# CPU_board.net
KiCad netlist of a schematic drawn in Altium Designer
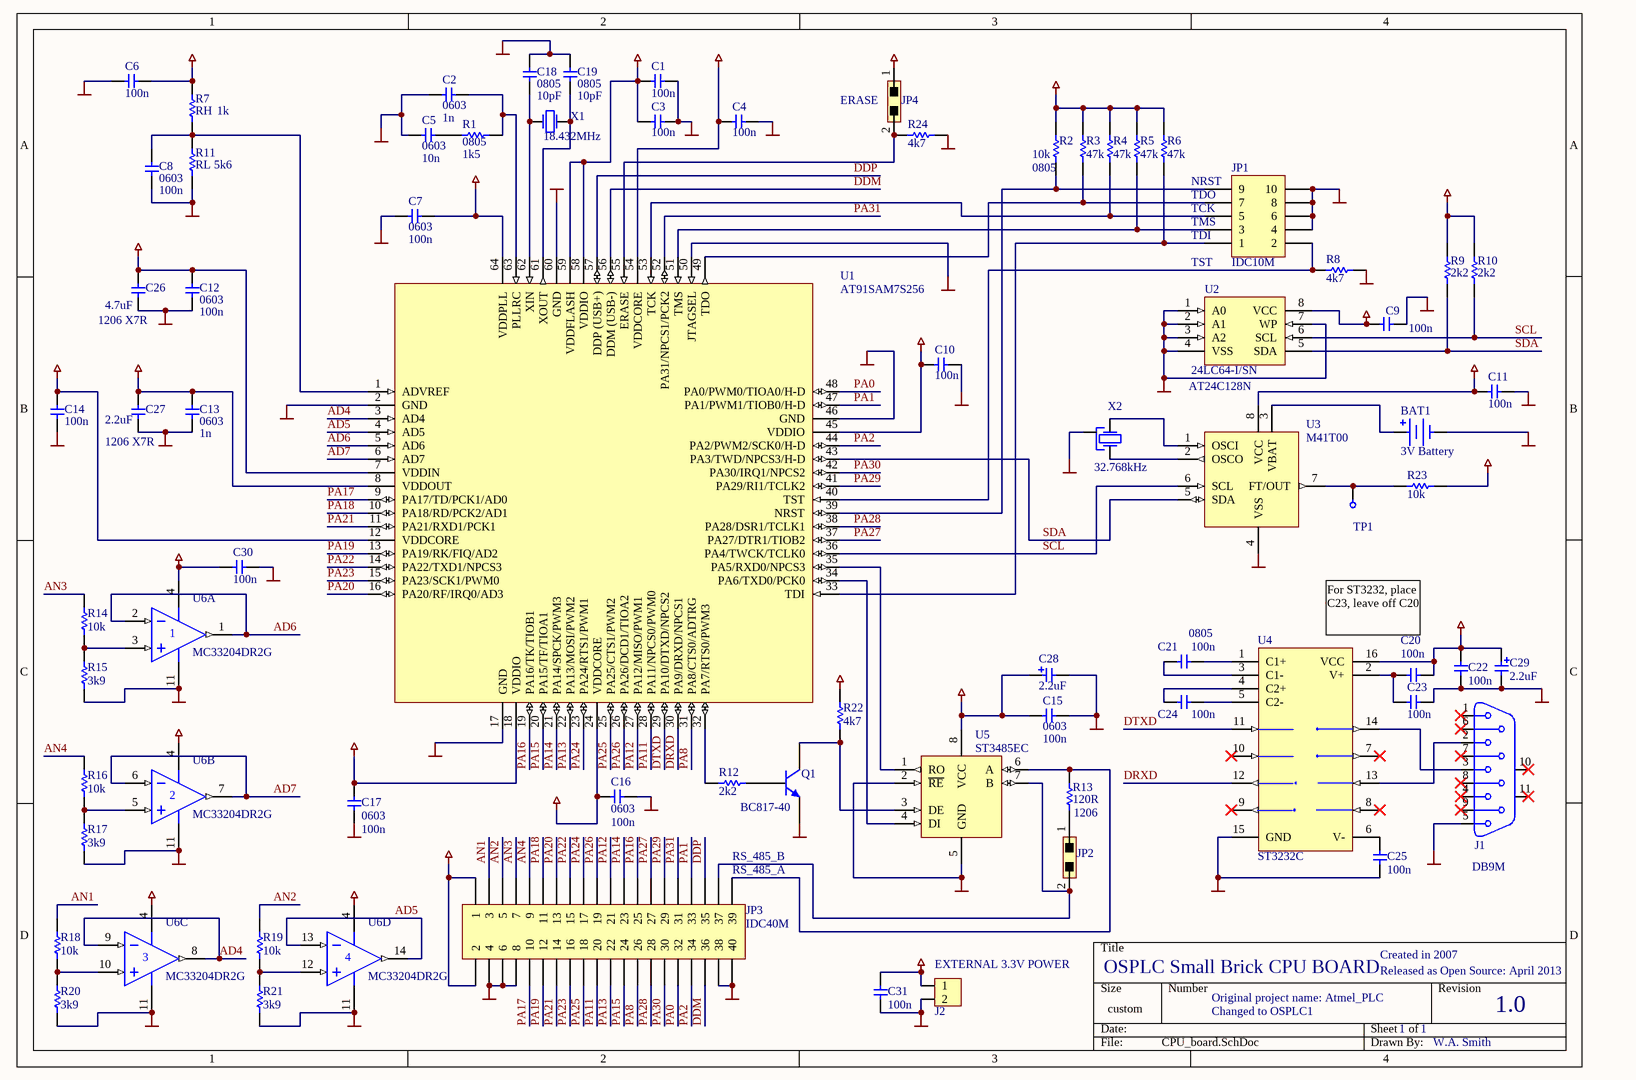
[diagram p0: CPU_board.SchDoc]

(export (version "E")
  (design (tool "Eeschema 10.0.6"))
  (components
    (comp (ref "BAT1")
      (value "3V Battery")
      (footprint "BATTERY_22MM")
      (description "3 Volt Lithium Button Battery")
      (libsource (lib "ARM_projects") (part "BATTERY_22MM"))
    )
    (comp (ref "C1")
      (value "0603")
      (footprint "0603")
      (description "0603 footprint non-polorised capacitor")
      (fields (field (name "ALTIUM_VALUE") "100n"))
      (libsource (lib "Integrated Comp_lib") (part "CAP_0603"))
    )
    (comp (ref "C2")
      (value "0603")
      (footprint "0603")
      (description "0603 footprint non-polorised capacitor")
      (fields (field (name "ALTIUM_VALUE") "1n"))
      (libsource (lib "Integrated Comp_lib") (part "CAP_0603"))
    )
    (comp (ref "C3")
      (value "0603")
      (footprint "0603")
      (description "0603 footprint non-polorised capacitor")
      (fields (field (name "ALTIUM_VALUE") "100n"))
      (libsource (lib "Integrated Comp_lib") (part "CAP_0603"))
    )
    (comp (ref "C4")
      (value "0603")
      (footprint "0603")
      (description "0603 footprint non-polorised capacitor")
      (fields (field (name "ALTIUM_VALUE") "100n"))
      (libsource (lib "Integrated Comp_lib") (part "CAP_0603"))
    )
    (comp (ref "C5")
      (value "0603")
      (footprint "0603")
      (description "0603 footprint non-polorised capacitor")
      (fields (field (name "ALTIUM_VALUE") "10n"))
      (libsource (lib "Integrated Comp_lib") (part "CAP_0603"))
    )
    (comp (ref "C6")
      (value "0603")
      (footprint "0603")
      (description "0603 footprint non-polorised capacitor")
      (fields (field (name "ALTIUM_VALUE") "100n"))
      (libsource (lib "Integrated Comp_lib") (part "CAP_0603"))
    )
    (comp (ref "C7")
      (value "0603")
      (footprint "0603")
      (description "0603 footprint non-polorised capacitor")
      (fields (field (name "ALTIUM_VALUE") "100n"))
      (libsource (lib "Integrated Comp_lib") (part "CAP_0603"))
    )
    (comp (ref "C8")
      (value "0603")
      (footprint "0603")
      (description "0603 footprint non-polorised capacitor")
      (fields (field (name "ALTIUM_VALUE") "100n"))
      (libsource (lib "Integrated Comp_lib") (part "CAP_0603"))
    )
    (comp (ref "C9")
      (value "0603")
      (footprint "0603")
      (description "0603 footprint non-polorised capacitor")
      (fields (field (name "ALTIUM_VALUE") "100n"))
      (libsource (lib "Integrated Comp_lib") (part "CAP_0603"))
    )
    (comp (ref "C10")
      (value "0603")
      (footprint "0603")
      (description "0603 footprint non-polorised capacitor")
      (fields (field (name "ALTIUM_VALUE") "100n"))
      (libsource (lib "Integrated Comp_lib") (part "CAP_0603"))
    )
    (comp (ref "C11")
      (value "0603")
      (footprint "0603")
      (description "0603 footprint non-polorised capacitor")
      (fields (field (name "ALTIUM_VALUE") "100n"))
      (libsource (lib "Integrated Comp_lib") (part "CAP_0603"))
    )
    (comp (ref "C12")
      (value "0603")
      (footprint "0603")
      (description "0603 footprint non-polorised capacitor")
      (fields (field (name "ALTIUM_VALUE") "100n"))
      (libsource (lib "Integrated Comp_lib") (part "CAP_0603"))
    )
    (comp (ref "C13")
      (value "0603")
      (footprint "0603")
      (description "0603 footprint non-polorised capacitor")
      (fields (field (name "ALTIUM_VALUE") "1n"))
      (libsource (lib "Integrated Comp_lib") (part "CAP_0603"))
    )
    (comp (ref "C14")
      (value "0603")
      (footprint "0603")
      (description "0603 footprint non-polorised capacitor")
      (fields (field (name "ALTIUM_VALUE") "100n"))
      (libsource (lib "Integrated Comp_lib") (part "CAP_0603"))
    )
    (comp (ref "C15")
      (value "0603")
      (footprint "0603")
      (description "0603 footprint non-polorised capacitor")
      (fields (field (name "ALTIUM_VALUE") "100n"))
      (libsource (lib "Integrated Comp_lib") (part "CAP_0603"))
    )
    (comp (ref "C16")
      (value "0603")
      (footprint "0603")
      (description "0603 footprint non-polorised capacitor")
      (fields (field (name "ALTIUM_VALUE") "100n"))
      (libsource (lib "Integrated Comp_lib") (part "CAP_0603"))
    )
    (comp (ref "C17")
      (value "0603")
      (footprint "0603")
      (description "0603 footprint non-polorised capacitor")
      (fields (field (name "ALTIUM_VALUE") "100n"))
      (libsource (lib "Integrated Comp_lib") (part "CAP_0603"))
    )
    (comp (ref "C18")
      (value "0805")
      (footprint "0805")
      (description "0805 footprint non-polarised capacitor")
      (fields (field (name "ALTIUM_VALUE") "10pF"))
      (libsource (lib "Integrated Comp_lib") (part "CAP_0805"))
    )
    (comp (ref "C19")
      (value "0805")
      (footprint "0805")
      (description "0805 footprint non-polarised capacitor")
      (fields (field (name "ALTIUM_VALUE") "10pF"))
      (libsource (lib "Integrated Comp_lib") (part "CAP_0805"))
    )
    (comp (ref "C20")
      (value "0805")
      (footprint "0805")
      (description "0805 footprint non-polarised capacitor")
      (fields (field (name "ALTIUM_VALUE") "100n"))
      (libsource (lib "Integrated Comp_lib") (part "CAP_0805"))
    )
    (comp (ref "C21")
      (value "0805")
      (footprint "0805")
      (description "0805 footprint non-polarised capacitor")
      (fields (field (name "ALTIUM_VALUE") "100n"))
      (libsource (lib "Integrated Comp_lib") (part "CAP_0805"))
    )
    (comp (ref "C22")
      (value "0805")
      (footprint "0805")
      (description "0805 footprint non-polarised capacitor")
      (fields (field (name "ALTIUM_VALUE") "100n"))
      (libsource (lib "Integrated Comp_lib") (part "CAP_0805"))
    )
    (comp (ref "C23")
      (value "0805")
      (footprint "0805")
      (description "0805 footprint non-polarised capacitor")
      (fields (field (name "ALTIUM_VALUE") "100n"))
      (libsource (lib "Integrated Comp_lib") (part "CAP_0805"))
    )
    (comp (ref "C24")
      (value "0805")
      (footprint "0805")
      (description "0805 footprint non-polarised capacitor")
      (fields (field (name "ALTIUM_VALUE") "100n"))
      (libsource (lib "Integrated Comp_lib") (part "CAP_0805"))
    )
    (comp (ref "C25")
      (value "0805")
      (footprint "0805")
      (description "0805 footprint non-polarised capacitor")
      (fields (field (name "ALTIUM_VALUE") "100n"))
      (libsource (lib "Integrated Comp_lib") (part "CAP_0805"))
    )
    (comp (ref "C26")
      (value "1206 X7R")
      (footprint "1206")
      (description "1206 footprint non-polorised capacitor")
      (fields (field (name "ALTIUM_VALUE") "4.7uF"))
      (libsource (lib "Integrated Comp_lib") (part "CAP_1206"))
    )
    (comp (ref "C27")
      (value "1206 X7R")
      (footprint "1206")
      (description "1206 footprint non-polorised capacitor")
      (fields (field (name "ALTIUM_VALUE") "2.2uF"))
      (libsource (lib "Integrated Comp_lib") (part "CAP_1206"))
    )
    (comp (ref "C28")
      (value "Tant_A")
      (footprint "CAP_TANT_A")
      (description "Tantalum Capacitor, A Package")
      (fields (field (name "ALTIUM_VALUE") "2.2uF"))
      (libsource (lib "Integrated Comp_lib") (part "CAP_TANT_A"))
    )
    (comp (ref "C29")
      (value "Tant_A")
      (footprint "CAP_TANT_A")
      (description "Tantalum Capacitor, A Package")
      (fields (field (name "ALTIUM_VALUE") "2.2uF"))
      (libsource (lib "Integrated Comp_lib") (part "CAP_TANT_A"))
    )
    (comp (ref "C30")
      (value "0603")
      (footprint "0603")
      (description "0603 footprint non-polorised capacitor")
      (fields (field (name "ALTIUM_VALUE") "100n"))
      (libsource (lib "Integrated Comp_lib") (part "CAP_0603"))
    )
    (comp (ref "C31")
      (value "0805")
      (footprint "0805")
      (description "0805 footprint non-polarised capacitor")
      (fields (field (name "ALTIUM_VALUE") "100n"))
      (libsource (lib "Integrated Comp_lib") (part "CAP_0805"))
    )
    (comp (ref "J1")
      (value "DB9M")
      (footprint "DB9M")
      (description "DB 9 Male connector")
      (libsource (lib "Integrated Comp_lib") (part "DB9M"))
    )
    (comp (ref "J2")
      (value "Mini Screw Terminal")
      (footprint "MINI_TERMINAL_2")
      (description "Mini Screw Terminal, 2.54mm Pitch")
      (libsource (lib "ARM_projects") (part "MINI_TERMINAL_2"))
    )
    (comp (ref "JP1")
      (value "IDC10M")
      (footprint "IDC_10M_BOX")
      (description "10 pin IDC male connector, vertical, box")
      (libsource (lib "Integrated Comp_lib") (part "IDC_10M"))
    )
    (comp (ref "JP2")
      (value "JUMPER2")
      (footprint "JUMPER2_254")
      (description "2 Pin Jumper, 2.54mm")
      (libsource (lib "ARM_projects") (part "JUMPER2"))
    )
    (comp (ref "JP3")
      (value "IDC40M")
      (footprint "IDC_40M_BOX")
      (description "40 pin IDC male connector, vertical, box")
      (libsource (lib "Integrated Comp_lib") (part "IDC_40M"))
    )
    (comp (ref "JP4")
      (value "JUMPER2")
      (footprint "JUMPER2_254")
      (description "2 Pin Jumper, 2.54mm")
      (libsource (lib "ARM_projects") (part "JUMPER2"))
    )
    (comp (ref "Q1")
      (value "BC817-40")
      (footprint "SO-G3/Y1")
      (description "NPN General Purpose Amplifier")
      (fields
        (field (name "MANUFACTURER") "Fairchild Semiconductor")
        (field (name "PUBLISHER") "Altium Limited")
      )
      (libsource (lib "FSC Discrete BJT") (part "BC817-40"))
    )
    (comp (ref "R1")
      (value "0805")
      (footprint "0805")
      (description "0805 footprint resistor")
      (fields (field (name "ALTIUM_VALUE") "1k5"))
      (libsource (lib "Integrated Comp_lib") (part "RES_0805"))
    )
    (comp (ref "R2")
      (value "0805")
      (footprint "0805")
      (description "0805 footprint resistor")
      (fields (field (name "ALTIUM_VALUE") "10k"))
      (libsource (lib "Integrated Comp_lib") (part "RES_0805"))
    )
    (comp (ref "R3")
      (value "0805")
      (footprint "0805")
      (description "0805 footprint resistor")
      (fields (field (name "ALTIUM_VALUE") "47k"))
      (libsource (lib "Integrated Comp_lib") (part "RES_0805"))
    )
    (comp (ref "R4")
      (value "0805")
      (footprint "0805")
      (description "0805 footprint resistor")
      (fields (field (name "ALTIUM_VALUE") "47k"))
      (libsource (lib "Integrated Comp_lib") (part "RES_0805"))
    )
    (comp (ref "R5")
      (value "0805")
      (footprint "0805")
      (description "0805 footprint resistor")
      (fields (field (name "ALTIUM_VALUE") "47k"))
      (libsource (lib "Integrated Comp_lib") (part "RES_0805"))
    )
    (comp (ref "R6")
      (value "0805")
      (footprint "0805")
      (description "0805 footprint resistor")
      (fields (field (name "ALTIUM_VALUE") "47k"))
      (libsource (lib "Integrated Comp_lib") (part "RES_0805"))
    )
    (comp (ref "R7")
      (value "0805")
      (footprint "0805")
      (description "0805 footprint resistor")
      (fields (field (name "ALTIUM_VALUE") "RH"))
      (libsource (lib "Integrated Comp_lib") (part "RES_0805"))
    )
    (comp (ref "R8")
      (value "0805")
      (footprint "0805")
      (description "0805 footprint resistor")
      (fields (field (name "ALTIUM_VALUE") "4k7"))
      (libsource (lib "Integrated Comp_lib") (part "RES_0805"))
    )
    (comp (ref "R9")
      (value "0805")
      (footprint "0805")
      (description "0805 footprint resistor")
      (fields (field (name "ALTIUM_VALUE") "2k2"))
      (libsource (lib "Integrated Comp_lib") (part "RES_0805"))
    )
    (comp (ref "R10")
      (value "0805")
      (footprint "0805")
      (description "0805 footprint resistor")
      (fields (field (name "ALTIUM_VALUE") "2k2"))
      (libsource (lib "Integrated Comp_lib") (part "RES_0805"))
    )
    (comp (ref "R11")
      (value "0805")
      (footprint "0805")
      (description "0805 footprint resistor")
      (fields (field (name "ALTIUM_VALUE") "RL"))
      (libsource (lib "Integrated Comp_lib") (part "RES_0805"))
    )
    (comp (ref "R12")
      (value "0805")
      (footprint "0805")
      (description "0805 footprint resistor")
      (fields (field (name "ALTIUM_VALUE") "2k2"))
      (libsource (lib "Integrated Comp_lib") (part "RES_0805"))
    )
    (comp (ref "R13")
      (value "1206")
      (footprint "1206")
      (description "1206 footprint resistor")
      (fields (field (name "ALTIUM_VALUE") "120R"))
      (libsource (lib "Integrated Comp_lib") (part "RES_1206"))
    )
    (comp (ref "R14")
      (value "0805")
      (footprint "0805")
      (description "0805 footprint resistor")
      (fields (field (name "ALTIUM_VALUE") "10k"))
      (libsource (lib "Integrated Comp_lib") (part "RES_0805"))
    )
    (comp (ref "R15")
      (value "0805")
      (footprint "0805")
      (description "0805 footprint resistor")
      (fields (field (name "ALTIUM_VALUE") "3k9"))
      (libsource (lib "Integrated Comp_lib") (part "RES_0805"))
    )
    (comp (ref "R16")
      (value "0805")
      (footprint "0805")
      (description "0805 footprint resistor")
      (fields (field (name "ALTIUM_VALUE") "10k"))
      (libsource (lib "Integrated Comp_lib") (part "RES_0805"))
    )
    (comp (ref "R17")
      (value "0805")
      (footprint "0805")
      (description "0805 footprint resistor")
      (fields (field (name "ALTIUM_VALUE") "3k9"))
      (libsource (lib "Integrated Comp_lib") (part "RES_0805"))
    )
    (comp (ref "R18")
      (value "0805")
      (footprint "0805")
      (description "0805 footprint resistor")
      (fields (field (name "ALTIUM_VALUE") "10k"))
      (libsource (lib "Integrated Comp_lib") (part "RES_0805"))
    )
    (comp (ref "R19")
      (value "0805")
      (footprint "0805")
      (description "0805 footprint resistor")
      (fields (field (name "ALTIUM_VALUE") "10k"))
      (libsource (lib "Integrated Comp_lib") (part "RES_0805"))
    )
    (comp (ref "R20")
      (value "0805")
      (footprint "0805")
      (description "0805 footprint resistor")
      (fields (field (name "ALTIUM_VALUE") "3k9"))
      (libsource (lib "Integrated Comp_lib") (part "RES_0805"))
    )
    (comp (ref "R21")
      (value "0805")
      (footprint "0805")
      (description "0805 footprint resistor")
      (fields (field (name "ALTIUM_VALUE") "3k9"))
      (libsource (lib "Integrated Comp_lib") (part "RES_0805"))
    )
    (comp (ref "R22")
      (value "0805")
      (footprint "0805")
      (description "0805 footprint resistor")
      (fields (field (name "ALTIUM_VALUE") "4k7"))
      (libsource (lib "Integrated Comp_lib") (part "RES_0805"))
    )
    (comp (ref "R23")
      (value "0805")
      (footprint "0805")
      (description "0805 footprint resistor")
      (fields (field (name "ALTIUM_VALUE") "10k"))
      (libsource (lib "Integrated Comp_lib") (part "RES_0805"))
    )
    (comp (ref "R24")
      (value "0805")
      (footprint "0805")
      (description "0805 footprint resistor")
      (fields (field (name "ALTIUM_VALUE") "4k7"))
      (libsource (lib "Integrated Comp_lib") (part "RES_0805"))
    )
    (comp (ref "TP1")
      (value "TEST POINT")
      (footprint "TEST_POINT")
      (libsource (lib "Integrated Comp_lib") (part "TEST_POINT"))
    )
    (comp (ref "U1")
      (value "AT91SAM7S256")
      (footprint "LQFP64-10-05")
      (description "Atmel ARM7 microcontroller, 256k Flash")
      (libsource (lib "ARM_projects") (part "AT91SAM7S256"))
    )
    (comp (ref "U2")
      (value "24LC64-I/SN")
      (footprint "SO-G8/Z7.4")
      (description "Microchip 64k bit I2C bus serial EEPROM")
      (fields (field (name "ALTIUM_VALUE") "AT24C128N"))
      (libsource (lib "Integrated Comp_lib") (part "24LC64-I/SN"))
    )
    (comp (ref "U3")
      (value "M41T00")
      (footprint "SO-G8/X.6")
      (description "ST Serial Access Timekeeper")
      (libsource (lib "Integrated Comp_lib") (part "M41T00"))
    )
    (comp (ref "U4")
      (value "ST3232C")
      (footprint "SO-G16/G6.9")
      (description "3.0V TO 5.5V, Low-Power, up to 1Mbps, True RS-232 Transceiver Using Four 0.1µF External Capacitor")
      (fields (field (name "MANUFACTURER") "Maxim") (field (name "PUBLISHER") "Altium Limited"))
      (libsource (lib "Maxim Communication Transceiver") (part "MAX3232CWE"))
    )
    (comp (ref "U5")
      (value "ST3485EC")
      (footprint "SO-G8/Z7.4")
      (description "ST 3.3v RS-485/RS-422 Transceiver")
      (libsource (lib "Integrated Comp_lib") (part "ST3485EC"))
    )
    (comp (ref "U6")
      (value "MC33204DR2G")
      (footprint "SO-G14/Y2.2")
      (description "Quad Low-Power Operational Amplifier")
      (fields (field (name "MANUFACTURER") "Motorola") (field (name "PUBLISHER") "Altium Limited"))
      (libsource (lib "Motorola Amplifier Operational Amplifier") (part "LM2902D"))
    )
    (comp (ref "X1")
      (value "18.432MHz")
      (footprint "CRYSTAL_SMT")
      (description "SMT crystal")
      (libsource (lib "ARM_projects") (part "CRYSTAL_SMT"))
    )
    (comp (ref "X2")
      (value "32.768kHz")
      (footprint "XTAL_TF")
      (description "Tuning Fork Crystal")
      (libsource (lib "Integrated Comp_lib") (part "CRYSTAL_TF"))
    )
  )
  (nets
    (net (code "1") (name "/AD4") (class "Default")
      (node (ref "U1") (pin "3") (pinfunction "AD4_3") (pintype "input"))
      (node (ref "U6") (pin "8") (pinfunction "OUT_8") (pintype "output"))
      (node (ref "U6") (pin "9") (pinfunction "IN-_9") (pintype "input"))
    )
    (net (code "2") (name "/AD5") (class "Default")
      (node (ref "U1") (pin "4") (pinfunction "AD5_4") (pintype "input"))
      (node (ref "U6") (pin "13") (pinfunction "IN-_13") (pintype "input"))
      (node (ref "U6") (pin "14") (pinfunction "OUT_14") (pintype "output"))
    )
    (net (code "3") (name "/AD6") (class "Default")
      (node (ref "U1") (pin "5") (pinfunction "AD6_5") (pintype "input"))
      (node (ref "U6") (pin "1") (pinfunction "OUT_1") (pintype "output"))
      (node (ref "U6") (pin "2") (pinfunction "IN-_2") (pintype "input"))
    )
    (net (code "4") (name "/AD7") (class "Default")
      (node (ref "U1") (pin "6") (pinfunction "AD7_6") (pintype "input"))
      (node (ref "U6") (pin "6") (pinfunction "IN-_6") (pintype "input"))
      (node (ref "U6") (pin "7") (pinfunction "OUT_7") (pintype "output"))
    )
    (net (code "5") (name "/AN1") (class "Default")
      (node (ref "JP3") (pin "3") (pinfunction "3_3") (pintype "passive"))
      (node (ref "R18") (pin "2") (pinfunction "2_2") (pintype "passive"))
    )
    (net (code "6") (name "/AN2") (class "Default")
      (node (ref "JP3") (pin "5") (pinfunction "5_5") (pintype "passive"))
      (node (ref "R19") (pin "2") (pinfunction "2_2") (pintype "passive"))
    )
    (net (code "7") (name "/AN3") (class "Default")
      (node (ref "JP3") (pin "7") (pinfunction "7_7") (pintype "passive"))
      (node (ref "R14") (pin "2") (pinfunction "2_2") (pintype "passive"))
    )
    (net (code "8") (name "/AN4") (class "Default")
      (node (ref "JP3") (pin "9") (pinfunction "9_9") (pintype "passive"))
      (node (ref "R16") (pin "2") (pinfunction "2_2") (pintype "passive"))
    )
    (net (code "9") (name "/DDM") (class "Default")
      (node (ref "JP3") (pin "36") (pinfunction "36_36") (pintype "passive"))
      (node (ref "U1") (pin "56") (pinfunction "DDM_(USB-)_56") (pintype "bidirectional"))
    )
    (net (code "10") (name "/DDP") (class "Default")
      (node (ref "JP3") (pin "35") (pinfunction "35_35") (pintype "passive"))
      (node (ref "U1") (pin "57") (pinfunction "DDP_(USB+)_57") (pintype "bidirectional"))
    )
    (net (code "11") (name "/DRXD") (class "Default")
      (node (ref "U1") (pin "30") (pinfunction "PA9/DRXD/NPCS1_30") (pintype "bidirectional"))
      (node (ref "U4") (pin "12") (pinfunction "R1OUT_12") (pintype "output"))
    )
    (net (code "12") (name "/DTXD") (class "Default")
      (node (ref "U1") (pin "29") (pinfunction "PA10/DTXD/NPCS2_29") (pintype "bidirectional"))
      (node (ref "U4") (pin "11") (pinfunction "T1IN_11") (pintype "input"))
    )
    (net (code "13") (name "/PA0") (class "Default")
      (node (ref "JP3") (pin "32") (pinfunction "32_32") (pintype "passive"))
      (node (ref "U1") (pin "48") (pinfunction "PA0/PWM0/TIOA0/H-D_48") (pintype "bidirectional"))
    )
    (net (code "14") (name "/PA1") (class "Default")
      (node (ref "JP3") (pin "33") (pinfunction "33_33") (pintype "passive"))
      (node (ref "U1") (pin "47") (pinfunction "PA1/PWM1/TIOB0/H-D_47") (pintype "bidirectional"))
    )
    (net (code "15") (name "/PA2") (class "Default")
      (node (ref "JP3") (pin "34") (pinfunction "34_34") (pintype "passive"))
      (node (ref "U1") (pin "44") (pinfunction "PA2/PWM2/SCK0/H-D_44") (pintype "bidirectional"))
    )
    (net (code "16") (name "/PA8") (class "Default")
      (node (ref "JP3") (pin "26") (pinfunction "26_26") (pintype "passive"))
      (node (ref "U1") (pin "31") (pinfunction "PA8/CTS0/ADTRG_31") (pintype "bidirectional"))
    )
    (net (code "17") (name "/PA11") (class "Default")
      (node (ref "JP3") (pin "20") (pinfunction "20_20") (pintype "passive"))
      (node (ref "U1") (pin "28") (pinfunction "PA11/NPCS0/PWM0_28") (pintype "bidirectional"))
    )
    (net (code "18") (name "/PA12") (class "Default")
      (node (ref "JP3") (pin "21") (pinfunction "21_21") (pintype "passive"))
      (node (ref "U1") (pin "27") (pinfunction "PA12/MISO/PWM1_27") (pintype "bidirectional"))
    )
    (net (code "19") (name "/PA13") (class "Default")
      (node (ref "JP3") (pin "22") (pinfunction "22_22") (pintype "passive"))
      (node (ref "U1") (pin "22") (pinfunction "PA13/MOSI/PWM2_22") (pintype "bidirectional"))
    )
    (net (code "20") (name "/PA14") (class "Default")
      (node (ref "JP3") (pin "23") (pinfunction "23_23") (pintype "passive"))
      (node (ref "U1") (pin "21") (pinfunction "PA14/SPCK/PWM3_21") (pintype "bidirectional"))
    )
    (net (code "21") (name "/PA15") (class "Default")
      (node (ref "JP3") (pin "24") (pinfunction "24_24") (pintype "passive"))
      (node (ref "U1") (pin "20") (pinfunction "PA15/TF/TIOA1_20") (pintype "bidirectional"))
    )
    (net (code "22") (name "/PA16") (class "Default")
      (node (ref "JP3") (pin "25") (pinfunction "25_25") (pintype "passive"))
      (node (ref "U1") (pin "19") (pinfunction "PA16/TK/TIOB1_19") (pintype "bidirectional"))
    )
    (net (code "23") (name "/PA17") (class "Default")
      (node (ref "JP3") (pin "10") (pinfunction "10_10") (pintype "passive"))
      (node (ref "U1") (pin "9") (pinfunction "PA17/TD/PCK1/AD0_9") (pintype "bidirectional"))
    )
    (net (code "24") (name "/PA18") (class "Default")
      (node (ref "JP3") (pin "11") (pinfunction "11_11") (pintype "passive"))
      (node (ref "U1") (pin "10") (pinfunction "PA18/RD/PCK2/AD1_10") (pintype "bidirectional"))
    )
    (net (code "25") (name "/PA19") (class "Default")
      (node (ref "JP3") (pin "12") (pinfunction "12_12") (pintype "passive"))
      (node (ref "U1") (pin "13") (pinfunction "PA19/RK/FIQ/AD2_13") (pintype "bidirectional"))
    )
    (net (code "26") (name "/PA20") (class "Default")
      (node (ref "JP3") (pin "13") (pinfunction "13_13") (pintype "passive"))
      (node (ref "U1") (pin "16") (pinfunction "PA20/RF/IRQ0/AD3_16") (pintype "bidirectional"))
    )
    (net (code "27") (name "/PA21") (class "Default")
      (node (ref "JP3") (pin "14") (pinfunction "14_14") (pintype "passive"))
      (node (ref "U1") (pin "11") (pinfunction "PA21/RXD1/PCK1_11") (pintype "bidirectional"))
    )
    (net (code "28") (name "/PA22") (class "Default")
      (node (ref "JP3") (pin "15") (pinfunction "15_15") (pintype "passive"))
      (node (ref "U1") (pin "14") (pinfunction "PA22/TXD1/NPCS3_14") (pintype "bidirectional"))
    )
    (net (code "29") (name "/PA23") (class "Default")
      (node (ref "JP3") (pin "16") (pinfunction "16_16") (pintype "passive"))
      (node (ref "U1") (pin "15") (pinfunction "PA23/SCK1/PWM0_15") (pintype "bidirectional"))
    )
    (net (code "30") (name "/PA24") (class "Default")
      (node (ref "JP3") (pin "17") (pinfunction "17_17") (pintype "passive"))
      (node (ref "U1") (pin "23") (pinfunction "PA24/RTS1/PWM1_23") (pintype "bidirectional"))
    )
    (net (code "31") (name "/PA25") (class "Default")
      (node (ref "JP3") (pin "18") (pinfunction "18_18") (pintype "passive"))
      (node (ref "U1") (pin "25") (pinfunction "PA25/CTS1/PWM2_25") (pintype "bidirectional"))
    )
    (net (code "32") (name "/PA26") (class "Default")
      (node (ref "JP3") (pin "19") (pinfunction "19_19") (pintype "passive"))
      (node (ref "U1") (pin "26") (pinfunction "PA26/DCD1/TIOA2_26") (pintype "bidirectional"))
    )
    (net (code "33") (name "/PA27") (class "Default")
      (node (ref "JP3") (pin "27") (pinfunction "27_27") (pintype "passive"))
      (node (ref "U1") (pin "37") (pinfunction "PA27/DTR1/TIOB2_37") (pintype "bidirectional"))
    )
    (net (code "34") (name "/PA28") (class "Default")
      (node (ref "JP3") (pin "28") (pinfunction "28_28") (pintype "passive"))
      (node (ref "U1") (pin "38") (pinfunction "PA28/DSR1/TCLK1_38") (pintype "bidirectional"))
    )
    (net (code "35") (name "/PA29") (class "Default")
      (node (ref "JP3") (pin "29") (pinfunction "29_29") (pintype "passive"))
      (node (ref "U1") (pin "41") (pinfunction "PA29/RI1/TCLK2_41") (pintype "bidirectional"))
    )
    (net (code "36") (name "/PA30") (class "Default")
      (node (ref "JP3") (pin "30") (pinfunction "30_30") (pintype "passive"))
      (node (ref "U1") (pin "42") (pinfunction "PA30/IRQ1/NPCS2_42") (pintype "bidirectional"))
    )
    (net (code "37") (name "/PA31") (class "Default")
      (node (ref "JP3") (pin "31") (pinfunction "31_31") (pintype "passive"))
      (node (ref "U1") (pin "52") (pinfunction "PA31/NPCS1/PCK2_52") (pintype "bidirectional"))
    )
    (net (code "38") (name "/SCL") (class "Default")
      (node (ref "R10") (pin "1") (pinfunction "1_1") (pintype "passive"))
      (node (ref "U1") (pin "36") (pinfunction "PA4/TWCK/TCLK0_36") (pintype "bidirectional"))
      (node (ref "U2") (pin "6") (pinfunction "SCL_6") (pintype "input"))
      (node (ref "U3") (pin "6") (pinfunction "SCL_6") (pintype "input"))
    )
    (net (code "39") (name "/SDA") (class "Default")
      (node (ref "R9") (pin "1") (pinfunction "1_1") (pintype "passive"))
      (node (ref "U1") (pin "43") (pinfunction "PA3/TWD/NPCS3/H-D_43") (pintype "bidirectional"))
      (node (ref "U2") (pin "5") (pinfunction "SDA_5") (pintype "open_collector"))
      (node (ref "U3") (pin "5") (pinfunction "SDA_5") (pintype "bidirectional"))
    )
    (net (code "40") (name "GND") (class "Default")
      (node (ref "BAT1") (pin "2") (pinfunction "NEG_2") (pintype "power_in"))
      (node (ref "C1") (pin "2") (pinfunction "2_2") (pintype "passive"))
      (node (ref "C10") (pin "1") (pinfunction "1_1") (pintype "passive"))
      (node (ref "C11") (pin "2") (pinfunction "2_2") (pintype "passive"))
      (node (ref "C12") (pin "1") (pinfunction "1_1") (pintype "passive"))
      (node (ref "C13") (pin "1") (pinfunction "1_1") (pintype "passive"))
      (node (ref "C14") (pin "1") (pinfunction "1_1") (pintype "passive"))
      (node (ref "C15") (pin "2") (pinfunction "2_2") (pintype "passive"))
      (node (ref "C16") (pin "2") (pinfunction "2_2") (pintype "passive"))
      (node (ref "C17") (pin "1") (pinfunction "1_1") (pintype "passive"))
      (node (ref "C18") (pin "2") (pinfunction "2_2") (pintype "passive"))
      (node (ref "C19") (pin "2") (pinfunction "2_2") (pintype "passive"))
      (node (ref "C2") (pin "1") (pinfunction "1_1") (pintype "passive"))
      (node (ref "C22") (pin "2") (pinfunction "2_2") (pintype "passive"))
      (node (ref "C23") (pin "1") (pinfunction "1_1") (pintype "passive"))
      (node (ref "C25") (pin "1") (pinfunction "1_1") (pintype "passive"))
      (node (ref "C26") (pin "1") (pinfunction "1_1") (pintype "passive"))
      (node (ref "C27") (pin "1") (pinfunction "1_1") (pintype "passive"))
      (node (ref "C28") (pin "2") (pinfunction "2_2") (pintype "passive"))
      (node (ref "C29") (pin "2") (pinfunction "2_2") (pintype "passive"))
      (node (ref "C3") (pin "2") (pinfunction "2_2") (pintype "passive"))
      (node (ref "C30") (pin "2") (pinfunction "2_2") (pintype "passive"))
      (node (ref "C31") (pin "1") (pinfunction "1_1") (pintype "passive"))
      (node (ref "C4") (pin "2") (pinfunction "2_2") (pintype "passive"))
      (node (ref "C5") (pin "1") (pinfunction "1_1") (pintype "passive"))
      (node (ref "C6") (pin "1") (pinfunction "1_1") (pintype "passive"))
      (node (ref "C7") (pin "1") (pinfunction "1_1") (pintype "passive"))
      (node (ref "C8") (pin "1") (pinfunction "1_1") (pintype "passive"))
      (node (ref "C9") (pin "2") (pinfunction "2_2") (pintype "passive"))
      (node (ref "J1") (pin "5") (pinfunction "5_5") (pintype "passive"))
      (node (ref "J2") (pin "2") (pinfunction "2_2") (pintype "passive"))
      (node (ref "JP1") (pin "10") (pinfunction "10_10") (pintype "passive"))
      (node (ref "JP1") (pin "4") (pinfunction "4_4") (pintype "passive"))
      (node (ref "JP1") (pin "6") (pinfunction "6_6") (pintype "passive"))
      (node (ref "JP1") (pin "8") (pinfunction "8_8") (pintype "passive"))
      (node (ref "JP3") (pin "38") (pinfunction "38_38") (pintype "passive"))
      (node (ref "JP3") (pin "4") (pinfunction "4_4") (pintype "passive"))
      (node (ref "JP3") (pin "40") (pinfunction "40_40") (pintype "passive"))
      (node (ref "JP3") (pin "6") (pinfunction "6_6") (pintype "passive"))
      (node (ref "JP3") (pin "8") (pinfunction "8_8") (pintype "passive"))
      (node (ref "Q1") (pin "2") (pinfunction "E_2") (pintype "passive"))
      (node (ref "R11") (pin "1") (pinfunction "1_1") (pintype "passive"))
      (node (ref "R15") (pin "1") (pinfunction "1_1") (pintype "passive"))
      (node (ref "R17") (pin "1") (pinfunction "1_1") (pintype "passive"))
      (node (ref "R20") (pin "1") (pinfunction "1_1") (pintype "passive"))
      (node (ref "R21") (pin "1") (pinfunction "1_1") (pintype "passive"))
      (node (ref "R24") (pin "2") (pinfunction "2_2") (pintype "passive"))
      (node (ref "R8") (pin "1") (pinfunction "1_1") (pintype "passive"))
      (node (ref "U1") (pin "17") (pinfunction "GND_17") (pintype "power_in"))
      (node (ref "U1") (pin "2") (pinfunction "GND_2") (pintype "power_in"))
      (node (ref "U1") (pin "46") (pinfunction "GND_46") (pintype "power_in"))
      (node (ref "U1") (pin "50") (pinfunction "JTAGSEL_50") (pintype "input"))
      (node (ref "U1") (pin "60") (pinfunction "GND_60") (pintype "power_in"))
      (node (ref "U2") (pin "1") (pinfunction "A0_1") (pintype "input"))
      (node (ref "U2") (pin "2") (pinfunction "A1_2") (pintype "input"))
      (node (ref "U2") (pin "3") (pinfunction "A2_3") (pintype "input"))
      (node (ref "U2") (pin "4") (pinfunction "VSS_4") (pintype "power_in"))
      (node (ref "U2") (pin "7") (pinfunction "WP_7") (pintype "input"))
      (node (ref "U3") (pin "4") (pinfunction "VSS_4") (pintype "power_in"))
      (node (ref "U4") (pin "15") (pinfunction "GND_15") (pintype "power_in"))
      (node (ref "U5") (pin "2") (pinfunction "~{RE}_2") (pintype "input"))
      (node (ref "U5") (pin "5") (pinfunction "GND_5") (pintype "power_in"))
      (node (ref "U6") (pin "11") (pinfunction "V-_11") (pintype "power_in"))
      (node (ref "X2") (pin "3") (pinfunction "X_3") (pintype "passive"))
    )
    (net (code "41") (name "Net-(BAT1-POS)") (class "Default")
      (node (ref "BAT1") (pin "1") (pinfunction "POS_1") (pintype "power_in"))
      (node (ref "U3") (pin "3") (pinfunction "VBAT_3") (pintype "power_in"))
    )
    (net (code "42") (name "Net-(C5-Pad2)") (class "Default")
      (node (ref "C5") (pin "2") (pinfunction "2_2") (pintype "passive"))
      (node (ref "R1") (pin "1") (pinfunction "1_1") (pintype "passive"))
    )
    (net (code "43") (name "Net-(JP2-Pad1)") (class "Default")
      (node (ref "JP2") (pin "1") (pinfunction "1_1") (pintype "passive"))
      (node (ref "R13") (pin "1") (pinfunction "1_1") (pintype "passive"))
    )
    (net (code "44") (name "Net-(Q1-B)") (class "Default")
      (node (ref "Q1") (pin "1") (pinfunction "B_1") (pintype "passive"))
      (node (ref "R12") (pin "1") (pinfunction "1_1") (pintype "passive"))
    )
    (net (code "45") (name "Net-(Q1-C)") (class "Default")
      (node (ref "Q1") (pin "3") (pinfunction "C_3") (pintype "passive"))
      (node (ref "R22") (pin "1") (pinfunction "1_1") (pintype "passive"))
      (node (ref "U5") (pin "3") (pinfunction "DE_3") (pintype "input"))
    )
    (net (code "46") (name "Net-(U1-ADVREF)") (class "Default")
      (node (ref "C8") (pin "2") (pinfunction "2_2") (pintype "passive"))
      (node (ref "R11") (pin "2") (pinfunction "2_2") (pintype "passive"))
      (node (ref "R7") (pin "1") (pinfunction "1_1") (pintype "passive"))
      (node (ref "U1") (pin "1") (pinfunction "ADVREF_1") (pintype "input"))
    )
    (net (code "47") (name "Net-(U1-ERASE)") (class "Default")
      (node (ref "JP4") (pin "2") (pinfunction "2_2") (pintype "passive"))
      (node (ref "R24") (pin "1") (pinfunction "1_1") (pintype "passive"))
      (node (ref "U1") (pin "55") (pinfunction "ERASE_55") (pintype "input"))
    )
    (net (code "48") (name "Net-(U1-NRST)") (class "Default")
      (node (ref "JP1") (pin "9") (pinfunction "9_9") (pintype "passive"))
      (node (ref "R2") (pin "1") (pinfunction "1_1") (pintype "passive"))
      (node (ref "U1") (pin "39") (pinfunction "NRST_39") (pintype "bidirectional"))
    )
    (net (code "49") (name "Net-(U1-PA5{slash}RXD0{slash}NPCS3)") (class "Default")
      (node (ref "U1") (pin "35") (pinfunction "PA5/RXD0/NPCS3_35") (pintype "bidirectional"))
      (node (ref "U5") (pin "1") (pinfunction "RO_1") (pintype "output"))
    )
    (net (code "50") (name "Net-(U1-PA6{slash}TXD0{slash}PCK0)") (class "Default")
      (node (ref "U1") (pin "34") (pinfunction "PA6/TXD0/PCK0_34") (pintype "bidirectional"))
      (node (ref "U5") (pin "4") (pinfunction "DI_4") (pintype "input"))
    )
    (net (code "51") (name "Net-(U1-PA7{slash}RTS0{slash}PWM3)") (class "Default")
      (node (ref "R12") (pin "2") (pinfunction "2_2") (pintype "passive"))
      (node (ref "U1") (pin "32") (pinfunction "PA7/RTS0/PWM3_32") (pintype "bidirectional"))
    )
    (net (code "52") (name "Net-(U1-PLLRC)") (class "Default")
      (node (ref "C2") (pin "2") (pinfunction "2_2") (pintype "passive"))
      (node (ref "R1") (pin "2") (pinfunction "2_2") (pintype "passive"))
      (node (ref "U1") (pin "63") (pinfunction "PLLRC_63") (pintype "input"))
    )
    (net (code "53") (name "Net-(U1-TCK)") (class "Default")
      (node (ref "JP1") (pin "5") (pinfunction "5_5") (pintype "passive"))
      (node (ref "R4") (pin "1") (pinfunction "1_1") (pintype "passive"))
      (node (ref "U1") (pin "53") (pinfunction "TCK_53") (pintype "input"))
    )
    (net (code "54") (name "Net-(U1-TDI)") (class "Default")
      (node (ref "JP1") (pin "1") (pinfunction "1_1") (pintype "passive"))
      (node (ref "R6") (pin "1") (pinfunction "1_1") (pintype "passive"))
      (node (ref "U1") (pin "33") (pinfunction "TDI_33") (pintype "input"))
    )
    (net (code "55") (name "Net-(U1-TDO)") (class "Default")
      (node (ref "JP1") (pin "7") (pinfunction "7_7") (pintype "passive"))
      (node (ref "R3") (pin "1") (pinfunction "1_1") (pintype "passive"))
      (node (ref "U1") (pin "49") (pinfunction "TDO_49") (pintype "output"))
    )
    (net (code "56") (name "Net-(U1-TMS)") (class "Default")
      (node (ref "JP1") (pin "3") (pinfunction "3_3") (pintype "passive"))
      (node (ref "R5") (pin "1") (pinfunction "1_1") (pintype "passive"))
      (node (ref "U1") (pin "51") (pinfunction "TMS_51") (pintype "input"))
    )
    (net (code "57") (name "Net-(U1-TST)") (class "Default")
      (node (ref "JP1") (pin "2") (pinfunction "2_2") (pintype "passive"))
      (node (ref "R8") (pin "2") (pinfunction "2_2") (pintype "passive"))
      (node (ref "U1") (pin "40") (pinfunction "TST_40") (pintype "input"))
    )
    (net (code "58") (name "Net-(U1-XIN)") (class "Default")
      (node (ref "C18") (pin "1") (pinfunction "1_1") (pintype "passive"))
      (node (ref "U1") (pin "62") (pinfunction "XIN_62") (pintype "input"))
      (node (ref "X1") (pin "1") (pinfunction "X_1") (pintype "passive"))
    )
    (net (code "59") (name "Net-(U1-XOUT)") (class "Default")
      (node (ref "C19") (pin "1") (pinfunction "1_1") (pintype "passive"))
      (node (ref "U1") (pin "61") (pinfunction "XOUT_61") (pintype "output"))
      (node (ref "X1") (pin "2") (pinfunction "X_2") (pintype "passive"))
    )
    (net (code "60") (name "Net-(U3-FT{slash}OUT)") (class "Default")
      (node (ref "R23") (pin "1") (pinfunction "1_1") (pintype "passive"))
      (node (ref "TP1") (pin "1") (pinfunction "1_1") (pintype "passive"))
      (node (ref "U3") (pin "7") (pinfunction "FT/OUT_7") (pintype "output"))
    )
    (net (code "61") (name "Net-(U3-OSCI)") (class "Default")
      (node (ref "U3") (pin "1") (pinfunction "OSCI_1") (pintype "input"))
      (node (ref "X2") (pin "1") (pinfunction "X_1") (pintype "passive"))
    )
    (net (code "62") (name "Net-(U3-OSCO)") (class "Default")
      (node (ref "U3") (pin "2") (pinfunction "OSCO_2") (pintype "output"))
      (node (ref "X2") (pin "2") (pinfunction "X_2") (pintype "passive"))
    )
    (net (code "63") (name "Net-(U4-C1+)") (class "Default")
      (node (ref "C21") (pin "1") (pinfunction "1_1") (pintype "passive"))
      (node (ref "U4") (pin "1") (pinfunction "C1+_1") (pintype "passive"))
    )
    (net (code "64") (name "Net-(U4-C1-)") (class "Default")
      (node (ref "C21") (pin "2") (pinfunction "2_2") (pintype "passive"))
      (node (ref "U4") (pin "3") (pinfunction "C1-_3") (pintype "passive"))
    )
    (net (code "65") (name "Net-(U4-C2+)") (class "Default")
      (node (ref "C24") (pin "2") (pinfunction "2_2") (pintype "passive"))
      (node (ref "U4") (pin "4") (pinfunction "C2+_4") (pintype "passive"))
    )
    (net (code "66") (name "Net-(U4-C2-)") (class "Default")
      (node (ref "C24") (pin "1") (pinfunction "1_1") (pintype "passive"))
      (node (ref "U4") (pin "5") (pinfunction "C2-_5") (pintype "passive"))
    )
    (net (code "67") (name "Net-(U4-R1IN)") (class "Default")
      (node (ref "J1") (pin "2") (pinfunction "2_2") (pintype "passive"))
      (node (ref "U4") (pin "13") (pinfunction "R1IN_13") (pintype "input"))
    )
    (net (code "68") (name "Net-(U4-T1OUT)") (class "Default")
      (node (ref "J1") (pin "3") (pinfunction "3_3") (pintype "passive"))
      (node (ref "U4") (pin "14") (pinfunction "T1OUT_14") (pintype "output"))
    )
    (net (code "69") (name "Net-(U4-V+)") (class "Default")
      (node (ref "C20") (pin "2") (pinfunction "2_2") (pintype "passive"))
      (node (ref "C23") (pin "2") (pinfunction "2_2") (pintype "passive"))
      (node (ref "U4") (pin "2") (pinfunction "V+_2") (pintype "power_in"))
    )
    (net (code "70") (name "Net-(U4-V-)") (class "Default")
      (node (ref "C25") (pin "2") (pinfunction "2_2") (pintype "passive"))
      (node (ref "U4") (pin "6") (pinfunction "V-_6") (pintype "power_in"))
    )
    (net (code "71") (name "Net-(U5-A)") (class "Default")
      (node (ref "JP3") (pin "39") (pinfunction "39_39") (pintype "passive"))
      (node (ref "R13") (pin "2") (pinfunction "2_2") (pintype "passive"))
      (node (ref "U5") (pin "6") (pinfunction "A_6") (pintype "bidirectional"))
    )
    (net (code "72") (name "Net-(U5-B)") (class "Default")
      (node (ref "JP2") (pin "2") (pinfunction "2_2") (pintype "passive"))
      (node (ref "JP3") (pin "37") (pinfunction "37_37") (pintype "passive"))
      (node (ref "U5") (pin "7") (pinfunction "B_7") (pintype "bidirectional"))
    )
    (net (code "73") (name "Net-(U6A-IN+)") (class "Default")
      (node (ref "R14") (pin "1") (pinfunction "1_1") (pintype "passive"))
      (node (ref "R15") (pin "2") (pinfunction "2_2") (pintype "passive"))
      (node (ref "U6") (pin "3") (pinfunction "IN+_3") (pintype "input"))
    )
    (net (code "74") (name "Net-(U6B-IN+)") (class "Default")
      (node (ref "R16") (pin "1") (pinfunction "1_1") (pintype "passive"))
      (node (ref "R17") (pin "2") (pinfunction "2_2") (pintype "passive"))
      (node (ref "U6") (pin "5") (pinfunction "IN+_5") (pintype "input"))
    )
    (net (code "75") (name "Net-(U6C-IN+)") (class "Default")
      (node (ref "R18") (pin "1") (pinfunction "1_1") (pintype "passive"))
      (node (ref "R20") (pin "2") (pinfunction "2_2") (pintype "passive"))
      (node (ref "U6") (pin "10") (pinfunction "IN+_10") (pintype "input"))
    )
    (net (code "76") (name "Net-(U6D-IN+)") (class "Default")
      (node (ref "R19") (pin "1") (pinfunction "1_1") (pintype "passive"))
      (node (ref "R21") (pin "2") (pinfunction "2_2") (pintype "passive"))
      (node (ref "U6") (pin "12") (pinfunction "IN+_12") (pintype "input"))
    )
    (net (code "77") (name "VCC1v8") (class "Default")
      (node (ref "C13") (pin "2") (pinfunction "2_2") (pintype "passive"))
      (node (ref "C14") (pin "2") (pinfunction "2_2") (pintype "passive"))
      (node (ref "C16") (pin "1") (pinfunction "1_1") (pintype "passive"))
      (node (ref "C27") (pin "2") (pinfunction "2_2") (pintype "passive"))
      (node (ref "C4") (pin "1") (pinfunction "1_1") (pintype "passive"))
      (node (ref "C7") (pin "2") (pinfunction "2_2") (pintype "passive"))
      (node (ref "U1") (pin "12") (pinfunction "VDDCORE_12") (pintype "power_in"))
      (node (ref "U1") (pin "24") (pinfunction "VDDCORE_24") (pintype "power_in"))
      (node (ref "U1") (pin "54") (pinfunction "VDDCORE_54") (pintype "power_in"))
      (node (ref "U1") (pin "64") (pinfunction "VDDPLL_64") (pintype "power_in"))
      (node (ref "U1") (pin "8") (pinfunction "VDDOUT_8") (pintype "power_in"))
    )
    (net (code "78") (name "VCC3v3") (class "Default")
      (node (ref "C1") (pin "1") (pinfunction "1_1") (pintype "passive"))
      (node (ref "C10") (pin "2") (pinfunction "2_2") (pintype "passive"))
      (node (ref "C11") (pin "1") (pinfunction "1_1") (pintype "passive"))
      (node (ref "C12") (pin "2") (pinfunction "2_2") (pintype "passive"))
      (node (ref "C15") (pin "1") (pinfunction "1_1") (pintype "passive"))
      (node (ref "C17") (pin "2") (pinfunction "2_2") (pintype "passive"))
      (node (ref "C20") (pin "1") (pinfunction "1_1") (pintype "passive"))
      (node (ref "C22") (pin "1") (pinfunction "1_1") (pintype "passive"))
      (node (ref "C26") (pin "2") (pinfunction "2_2") (pintype "passive"))
      (node (ref "C28") (pin "1") (pinfunction "1_1") (pintype "passive"))
      (node (ref "C29") (pin "1") (pinfunction "1_1") (pintype "passive"))
      (node (ref "C3") (pin "1") (pinfunction "1_1") (pintype "passive"))
      (node (ref "C30") (pin "1") (pinfunction "1_1") (pintype "passive"))
      (node (ref "C31") (pin "2") (pinfunction "2_2") (pintype "passive"))
      (node (ref "C6") (pin "2") (pinfunction "2_2") (pintype "passive"))
      (node (ref "C9") (pin "1") (pinfunction "1_1") (pintype "passive"))
      (node (ref "J2") (pin "1") (pinfunction "1_1") (pintype "passive"))
      (node (ref "JP3") (pin "1") (pinfunction "1_1") (pintype "passive"))
      (node (ref "JP3") (pin "2") (pinfunction "2_2") (pintype "passive"))
      (node (ref "JP4") (pin "1") (pinfunction "1_1") (pintype "passive"))
      (node (ref "R10") (pin "2") (pinfunction "2_2") (pintype "passive"))
      (node (ref "R2") (pin "2") (pinfunction "2_2") (pintype "passive"))
      (node (ref "R22") (pin "2") (pinfunction "2_2") (pintype "passive"))
      (node (ref "R23") (pin "2") (pinfunction "2_2") (pintype "passive"))
      (node (ref "R3") (pin "2") (pinfunction "2_2") (pintype "passive"))
      (node (ref "R4") (pin "2") (pinfunction "2_2") (pintype "passive"))
      (node (ref "R5") (pin "2") (pinfunction "2_2") (pintype "passive"))
      (node (ref "R6") (pin "2") (pinfunction "2_2") (pintype "passive"))
      (node (ref "R7") (pin "2") (pinfunction "2_2") (pintype "passive"))
      (node (ref "R9") (pin "2") (pinfunction "2_2") (pintype "passive"))
      (node (ref "U1") (pin "18") (pinfunction "VDDIO_18") (pintype "power_in"))
      (node (ref "U1") (pin "45") (pinfunction "VDDIO_45") (pintype "power_in"))
      (node (ref "U1") (pin "58") (pinfunction "VDDIO_58") (pintype "power_in"))
      (node (ref "U1") (pin "59") (pinfunction "VDDFLASH_59") (pintype "power_in"))
      (node (ref "U1") (pin "7") (pinfunction "VDDIN_7") (pintype "power_in"))
      (node (ref "U2") (pin "8") (pinfunction "VCC_8") (pintype "power_in"))
      (node (ref "U3") (pin "8") (pinfunction "VCC_8") (pintype "power_in"))
      (node (ref "U4") (pin "16") (pinfunction "VCC_16") (pintype "power_in"))
      (node (ref "U5") (pin "8") (pinfunction "VCC_8") (pintype "power_in"))
      (node (ref "U6") (pin "4") (pinfunction "V+_4") (pintype "power_in"))
    )
    (net (code "79") (name "unconnected-(J1-Pad1)") (class "Default")
      (node (ref "J1") (pin "1") (pinfunction "1_1") (pintype "passive+no_connect"))
    )
    (net (code "80") (name "unconnected-(J1-Pad4)") (class "Default")
      (node (ref "J1") (pin "4") (pinfunction "4_4") (pintype "passive+no_connect"))
    )
    (net (code "81") (name "unconnected-(J1-Pad6)") (class "Default")
      (node (ref "J1") (pin "6") (pinfunction "6_6") (pintype "passive+no_connect"))
    )
    (net (code "82") (name "unconnected-(J1-Pad7)") (class "Default")
      (node (ref "J1") (pin "7") (pinfunction "7_7") (pintype "passive+no_connect"))
    )
    (net (code "83") (name "unconnected-(J1-Pad8)") (class "Default")
      (node (ref "J1") (pin "8") (pinfunction "8_8") (pintype "passive+no_connect"))
    )
    (net (code "84") (name "unconnected-(J1-Pad9)") (class "Default")
      (node (ref "J1") (pin "9") (pinfunction "9_9") (pintype "passive+no_connect"))
    )
    (net (code "85") (name "unconnected-(J1-Pad10)") (class "Default")
      (node (ref "J1") (pin "10") (pinfunction "10_10") (pintype "passive+no_connect"))
    )
    (net (code "86") (name "unconnected-(J1-Pad11)") (class "Default")
      (node (ref "J1") (pin "11") (pinfunction "11_11") (pintype "passive+no_connect"))
    )
    (net (code "87") (name "unconnected-(U4-R2IN-Pad8)") (class "Default")
      (node (ref "U4") (pin "8") (pinfunction "R2IN_8") (pintype "input+no_connect"))
    )
    (net (code "88") (name "unconnected-(U4-R2OUT-Pad9)") (class "Default")
      (node (ref "U4") (pin "9") (pinfunction "R2OUT_9") (pintype "output+no_connect"))
    )
    (net (code "89") (name "unconnected-(U4-T2IN-Pad10)") (class "Default")
      (node (ref "U4") (pin "10") (pinfunction "T2IN_10") (pintype "input+no_connect"))
    )
    (net (code "90") (name "unconnected-(U4-T2OUT-Pad7)") (class "Default")
      (node (ref "U4") (pin "7") (pinfunction "T2OUT_7") (pintype "output+no_connect"))
    )
  )
)
